# Sine_Wave_Generator.net
KiCad netlist of a schematic drawn in Altium Designer
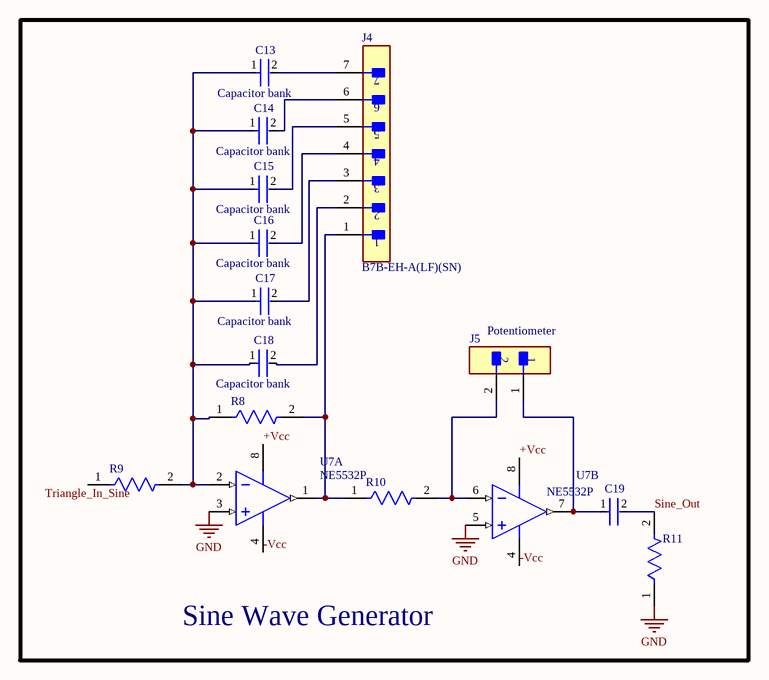
[diagram p0: Sine_Wave_Generator.SchDoc]

(export (version "E")
  (design (tool "Eeschema 10.0.6"))
  (components
    (comp (ref "C13")
      (value "Capacitor bank")
      (footprint "FP-F471K33Y5RP6UK5R-MFG")
      (description "CAP CER 470PF 2KV Y5R RADIAL")
      (fields (field (name "TOLERANCE") "10%") (field (name "VOLTAGE") "2kV"))
      (libsource (lib "Altium Content Vault") (part "b4654b650e69147ec39a6b967a45e02"))
    )
    (comp (ref "C14")
      (value "Capacitor bank")
      (footprint "FP-F471K33Y5RP6UK5R-MFG")
      (description "CAP CER 470PF 2KV Y5R RADIAL")
      (fields (field (name "TOLERANCE") "10%") (field (name "VOLTAGE") "2kV"))
      (libsource (lib "Altium Content Vault") (part "b4654b650e69147ec39a6b967a45e02"))
    )
    (comp (ref "C15")
      (value "Capacitor bank")
      (footprint "FP-F471K33Y5RP6UK5R-MFG")
      (description "CAP CER 470PF 2KV Y5R RADIAL")
      (fields (field (name "TOLERANCE") "10%") (field (name "VOLTAGE") "2kV"))
      (libsource (lib "Altium Content Vault") (part "b4654b650e69147ec39a6b967a45e02"))
    )
    (comp (ref "C16")
      (value "Capacitor bank")
      (footprint "FP-F471K33Y5RP6UK5R-MFG")
      (description "CAP CER 470PF 2KV Y5R RADIAL")
      (fields (field (name "TOLERANCE") "10%") (field (name "VOLTAGE") "2kV"))
      (libsource (lib "Altium Content Vault") (part "b4654b650e69147ec39a6b967a45e02"))
    )
    (comp (ref "C17")
      (value "Capacitor bank")
      (footprint "FP-F471K33Y5RP6UK5R-MFG")
      (description "CAP CER 470PF 2KV Y5R RADIAL")
      (fields (field (name "TOLERANCE") "10%") (field (name "VOLTAGE") "2kV"))
      (libsource (lib "Altium Content Vault") (part "b4654b650e69147ec39a6b967a45e02"))
    )
    (comp (ref "C18")
      (value "Capacitor bank")
      (footprint "FP-F471K33Y5RP6UK5R-MFG")
      (description "CAP CER 470PF 2KV Y5R RADIAL")
      (fields (field (name "TOLERANCE") "10%") (field (name "VOLTAGE") "2kV"))
      (libsource (lib "Altium Content Vault") (part "b4654b650e69147ec39a6b967a45e02"))
    )
    (comp (ref "C19")
      (value "~")
      (footprint "FP-F471K33Y5RP6UK5R-MFG")
      (description "CAP CER 470PF 2KV Y5R RADIAL")
      (fields (field (name "TOLERANCE") "10%") (field (name "VOLTAGE") "2kV"))
      (libsource (lib "Altium Content Vault") (part "b4654b650e69147ec39a6b967a45e02"))
    )
    (comp (ref "J4")
      (value "B7B-EH-A(LF)(SN)")
      (footprint "FP-B7B-EH-A_LF_SN-MFG")
      (description "CONN HEADER VERT 7POS 2.5MM")
      (libsource (lib "Altium Content Vault") (part "5bcee6b94e1fee4be3f4cc3a650a442"))
    )
    (comp (ref "J5")
      (value "Potentiometer")
      (footprint "FP-B2B-XH-A_LF_SN-MFG")
      (description "CONN HEADER VERT 2POS 2.5MM")
      (libsource (lib "Altium Content Vault") (part "3bc925449376181038e59eaffc5286c"))
    )
    (comp (ref "R8")
      (value "~")
      (footprint "FP-VR37-MFG")
      (description "RES 1.2M OHM 5% 1/2W AXIAL")
      (fields (field (name "TOLERANCE") "5%"))
      (libsource (lib "Altium Content Vault") (part "1029c3af85768c4190bb7ad29bc67b5"))
    )
    (comp (ref "R9")
      (value "~")
      (footprint "FP-VR37-MFG")
      (description "RES 1.2M OHM 5% 1/2W AXIAL")
      (fields (field (name "TOLERANCE") "5%"))
      (libsource (lib "Altium Content Vault") (part "1029c3af85768c4190bb7ad29bc67b5"))
    )
    (comp (ref "R10")
      (value "~")
      (footprint "FP-VR37-MFG")
      (description "RES 1.2M OHM 5% 1/2W AXIAL")
      (fields (field (name "TOLERANCE") "5%"))
      (libsource (lib "Altium Content Vault") (part "1029c3af85768c4190bb7ad29bc67b5"))
    )
    (comp (ref "R11")
      (value "~")
      (footprint "FP-VR37-MFG")
      (description "RES 1.2M OHM 5% 1/2W AXIAL")
      (fields (field (name "TOLERANCE") "5%"))
      (libsource (lib "Altium Content Vault") (part "1029c3af85768c4190bb7ad29bc67b5"))
    )
    (comp (ref "U7")
      (value "NE5532P")
      (footprint "P0008A")
      (fields (field (name "MANUFACTURER") "Texas Instruments"))
      (libsource (lib "Altium Content Vault") (part "TI-AMP-D6-2-8_D"))
    )
  )
  (nets
    (net (code "1") (name "/+Vcc") (class "Default")
      (node (ref "U7") (pin "8") (pinfunction "VCC+_8") (pintype "power_in"))
    )
    (net (code "2") (name "/-Vcc") (class "Default")
      (node (ref "U7") (pin "4") (pinfunction "VCC-_4") (pintype "power_in"))
    )
    (net (code "3") (name "/Sine_Out") (class "Default")
      (node (ref "C19") (pin "2") (pinfunction "2_2") (pintype "passive"))
      (node (ref "R11") (pin "2") (pinfunction "2_2") (pintype "passive"))
    )
    (net (code "4") (name "/Triangle_In_Sine") (class "Default")
      (node (ref "R9") (pin "1") (pinfunction "1_1") (pintype "passive"))
    )
    (net (code "5") (name "GND") (class "Default")
      (node (ref "R11") (pin "1") (pinfunction "1_1") (pintype "passive"))
      (node (ref "U7") (pin "3") (pinfunction "IN1+_3") (pintype "input"))
      (node (ref "U7") (pin "5") (pinfunction "IN2+_5") (pintype "input"))
    )
    (net (code "6") (name "Net-(C13-Pad2)") (class "Default")
      (node (ref "C13") (pin "2") (pinfunction "2_2") (pintype "passive"))
      (node (ref "J4") (pin "7") (pinfunction "7_7") (pintype "passive"))
    )
    (net (code "7") (name "Net-(C14-Pad2)") (class "Default")
      (node (ref "C14") (pin "2") (pinfunction "2_2") (pintype "passive"))
      (node (ref "J4") (pin "6") (pinfunction "6_6") (pintype "passive"))
    )
    (net (code "8") (name "Net-(C15-Pad2)") (class "Default")
      (node (ref "C15") (pin "2") (pinfunction "2_2") (pintype "passive"))
      (node (ref "J4") (pin "5") (pinfunction "5_5") (pintype "passive"))
    )
    (net (code "9") (name "Net-(C16-Pad2)") (class "Default")
      (node (ref "C16") (pin "2") (pinfunction "2_2") (pintype "passive"))
      (node (ref "J4") (pin "4") (pinfunction "4_4") (pintype "passive"))
    )
    (net (code "10") (name "Net-(C17-Pad2)") (class "Default")
      (node (ref "C17") (pin "2") (pinfunction "2_2") (pintype "passive"))
      (node (ref "J4") (pin "3") (pinfunction "3_3") (pintype "passive"))
    )
    (net (code "11") (name "Net-(C18-Pad2)") (class "Default")
      (node (ref "C18") (pin "2") (pinfunction "2_2") (pintype "passive"))
      (node (ref "J4") (pin "2") (pinfunction "2_2") (pintype "passive"))
    )
    (net (code "12") (name "Net-(U7A-IN1-)") (class "Default")
      (node (ref "C13") (pin "1") (pinfunction "1_1") (pintype "passive"))
      (node (ref "C14") (pin "1") (pinfunction "1_1") (pintype "passive"))
      (node (ref "C15") (pin "1") (pinfunction "1_1") (pintype "passive"))
      (node (ref "C16") (pin "1") (pinfunction "1_1") (pintype "passive"))
      (node (ref "C17") (pin "1") (pinfunction "1_1") (pintype "passive"))
      (node (ref "C18") (pin "1") (pinfunction "1_1") (pintype "passive"))
      (node (ref "R8") (pin "1") (pinfunction "1_1") (pintype "passive"))
      (node (ref "R9") (pin "2") (pinfunction "2_2") (pintype "passive"))
      (node (ref "U7") (pin "2") (pinfunction "IN1-_2") (pintype "input"))
    )
    (net (code "13") (name "Net-(U7A-OUT1)") (class "Default")
      (node (ref "J4") (pin "1") (pinfunction "1_1") (pintype "passive"))
      (node (ref "R10") (pin "1") (pinfunction "1_1") (pintype "passive"))
      (node (ref "R8") (pin "2") (pinfunction "2_2") (pintype "passive"))
      (node (ref "U7") (pin "1") (pinfunction "OUT1_1") (pintype "output"))
    )
    (net (code "14") (name "Net-(U7B-IN2-)") (class "Default")
      (node (ref "J5") (pin "2") (pinfunction "2_2") (pintype "passive"))
      (node (ref "R10") (pin "2") (pinfunction "2_2") (pintype "passive"))
      (node (ref "U7") (pin "6") (pinfunction "IN2-_6") (pintype "input"))
    )
    (net (code "15") (name "Net-(U7B-OUT2)") (class "Default")
      (node (ref "C19") (pin "1") (pinfunction "1_1") (pintype "passive"))
      (node (ref "J5") (pin "1") (pinfunction "1_1") (pintype "passive"))
      (node (ref "U7") (pin "7") (pinfunction "OUT2_7") (pintype "output"))
    )
  )
)
